# EthernetMagJack.net
KiCad netlist of a schematic drawn in Altium Designer
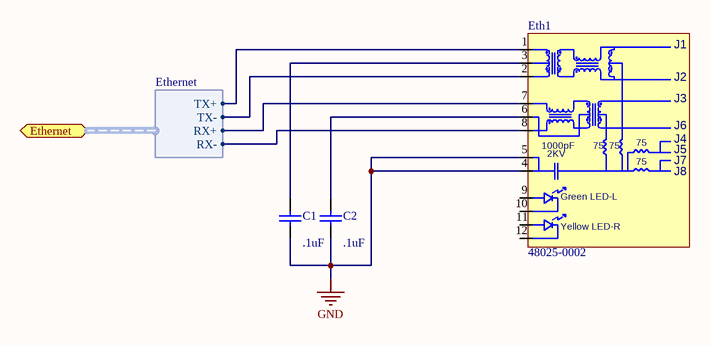
[diagram p0: EthernetMagJack.SchDoc]

(export (version "E")
  (design (tool "Eeschema 10.0.6"))
  (components
    (comp (ref "C1")
      (value ".1uF")
      (footprint "0402")
      (description "Capacitor (Semiconductor SIM Model)")
      (fields (field (name "Comment") "Cap Semi") (field (name "PUBLISHER") "Altium Limited"))
      (libsource (lib "Miscellaneous Devices") (part "Cap Semi"))
    )
    (comp (ref "C2")
      (value ".1uF")
      (footprint "0402")
      (description "Capacitor (Semiconductor SIM Model)")
      (fields (field (name "Comment") "Cap Semi") (field (name "PUBLISHER") "Altium Limited"))
      (libsource (lib "Miscellaneous Devices") (part "Cap Semi"))
    )
    (comp (ref "Eth1")
      (value "48025-0002")
      (footprint "MolexModularJacks:48025-0002")
      (description "Modular RJ45 Jack w/ Magnetics & LEDs")
      (libsource (lib "MolexModularJacks") (part "48025-0002"))
    )
  )
  (nets
    (net (code "2") (name "/RX+") (class "Default")
      (node (ref "Eth1") (pin "7") (pinfunction "7_7") (pintype "passive"))
    )
    (net (code "3") (name "/RX-") (class "Default")
      (node (ref "Eth1") (pin "8") (pinfunction "8_8") (pintype "passive"))
    )
    (net (code "4") (name "/TX+") (class "Default")
      (node (ref "Eth1") (pin "1") (pinfunction "1_1") (pintype "passive"))
    )
    (net (code "5") (name "/TX-") (class "Default")
      (node (ref "Eth1") (pin "2") (pinfunction "2_2") (pintype "passive"))
    )
    (net (code "7") (name "GND") (class "Default")
      (node (ref "C1") (pin "1") (pinfunction "1_1") (pintype "passive"))
      (node (ref "C2") (pin "1") (pinfunction "1_1") (pintype "passive"))
      (node (ref "Eth1") (pin "4") (pinfunction "4_4") (pintype "passive"))
      (node (ref "Eth1") (pin "5") (pinfunction "5_5") (pintype "passive"))
    )
    (net (code "8") (name "Net-(C1-Pad2)") (class "Default")
      (node (ref "C1") (pin "2") (pinfunction "2_2") (pintype "passive"))
      (node (ref "Eth1") (pin "3") (pinfunction "3_3") (pintype "passive"))
    )
    (net (code "9") (name "Net-(C2-Pad2)") (class "Default")
      (node (ref "C2") (pin "2") (pinfunction "2_2") (pintype "passive"))
      (node (ref "Eth1") (pin "6") (pinfunction "6_6") (pintype "passive"))
    )
    (net (code "10") (name "unconnected-(Eth1-Pad9)") (class "Default")
      (node (ref "Eth1") (pin "9") (pinfunction "9_9") (pintype "passive"))
    )
    (net (code "11") (name "unconnected-(Eth1-Pad10)") (class "Default")
      (node (ref "Eth1") (pin "10") (pinfunction "10_10") (pintype "passive"))
    )
    (net (code "12") (name "unconnected-(Eth1-Pad11)") (class "Default")
      (node (ref "Eth1") (pin "11") (pinfunction "11_11") (pintype "passive"))
    )
    (net (code "13") (name "unconnected-(Eth1-Pad12)") (class "Default")
      (node (ref "Eth1") (pin "12") (pinfunction "12_12") (pintype "passive"))
    )
  )
)
